# ESP32-S3-UNO_Easyeda_pro.net
KiCad netlist of a schematic drawn in EasyEDA Pro
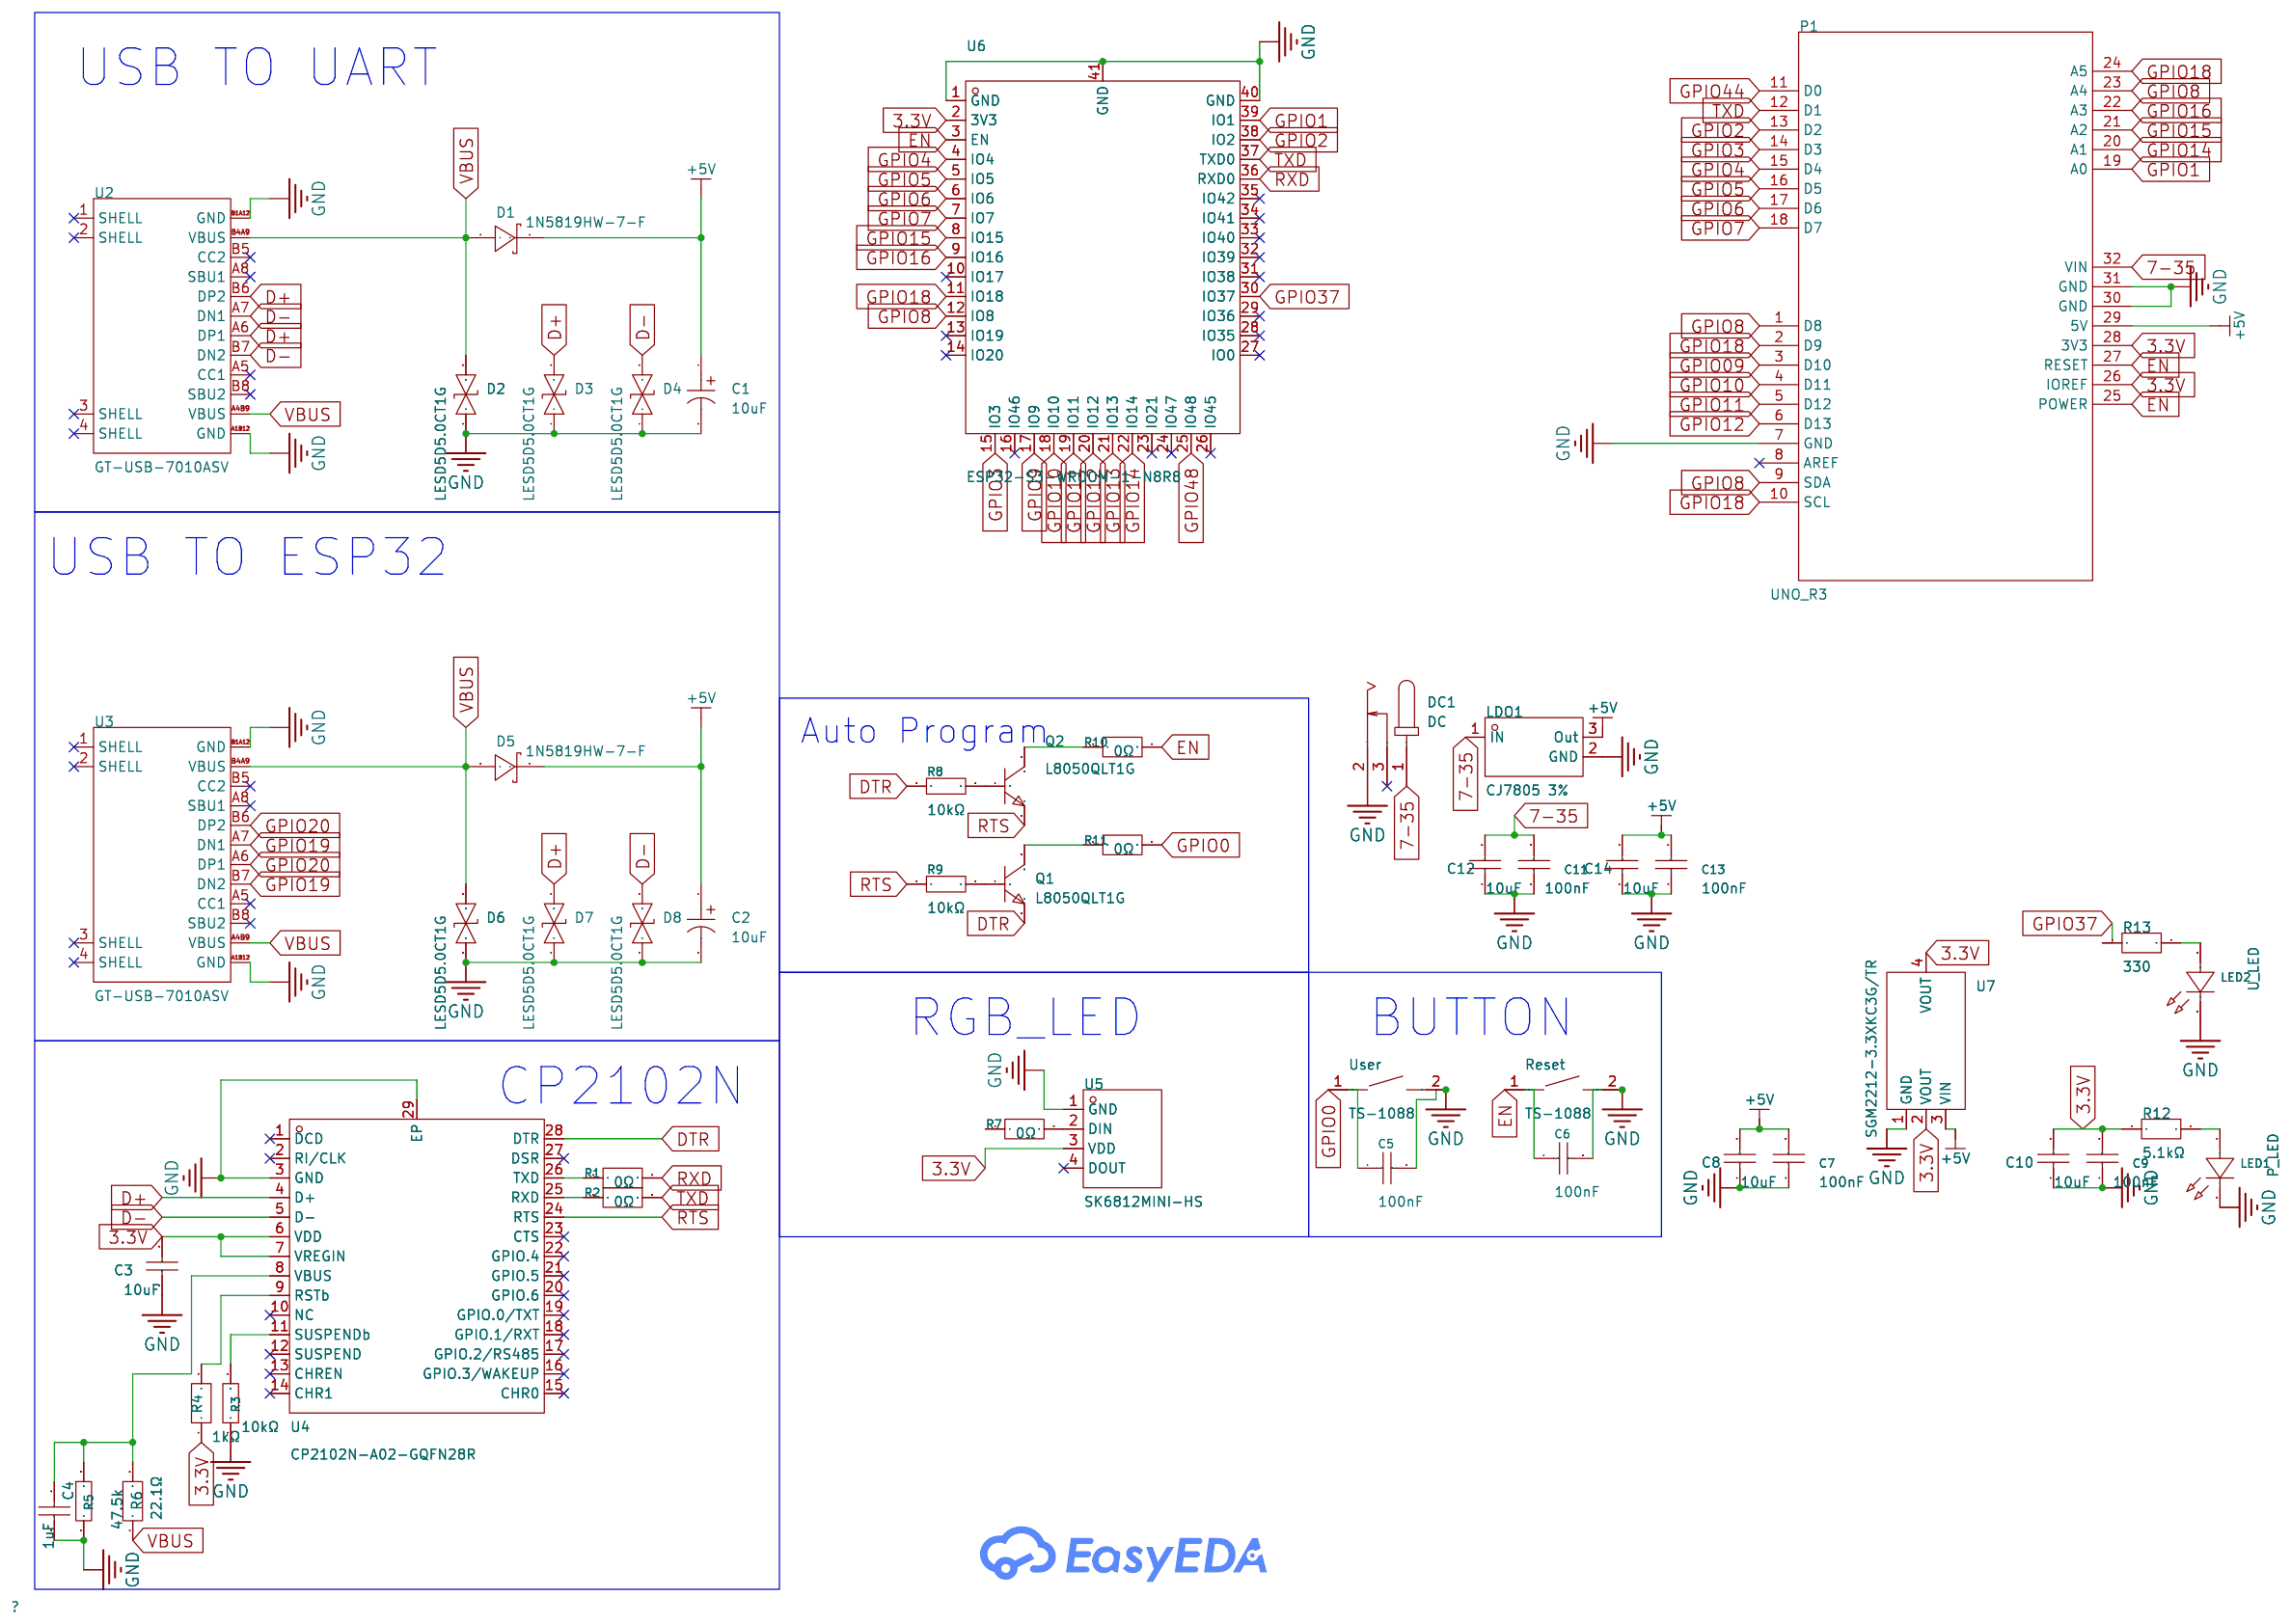
[diagram p0: schematic sheet]

(export (version "E")
  (design (tool "Eeschema 10.0.6"))
  (components
    (comp (ref "C1")
      (value "10uF")
      (footprint "easyedapro:CAP-SMD_BD4.0-L4.3-W4.3-FD-LS5.3")
      (fields
        (field (name "Manufacturer Part") "EFVH025ADA100M0454")
        (field (name "Manufacturer") "FOLLON(富隆电子)")
      )
      (libsource (lib "easyedapro") (part "EFVH025ADA100M0454"))
    )
    (comp (ref "C2")
      (value "10uF")
      (footprint "easyedapro:CAP-SMD_BD4.0-L4.3-W4.3-FD-LS5.3")
      (fields
        (field (name "Manufacturer Part") "EFVH025ADA100M0454")
        (field (name "Manufacturer") "FOLLON(富隆电子)")
      )
      (libsource (lib "easyedapro") (part "EFVH025ADA100M0454"))
    )
    (comp (ref "C3")
      (value "10uF")
      (footprint "easyedapro:C1206")
      (fields
        (field (name "Manufacturer Part") "CL31A106KBHNNNE")
        (field (name "Manufacturer") "SAMSUNG(三星)")
      )
      (libsource (lib "easyedapro") (part "CL31A106KBHNNNE"))
    )
    (comp (ref "C4")
      (value "1uF")
      (footprint "easyedapro:C1206")
      (fields
        (field (name "Manufacturer Part") "CL31B105KAHNNNE")
        (field (name "Manufacturer") "SAMSUNG(三星)")
      )
      (libsource (lib "easyedapro") (part "CL31B105KAHNNNE"))
    )
    (comp (ref "C5")
      (value "100nF")
      (footprint "easyedapro:C1206")
      (fields
        (field (name "Manufacturer Part") "CL31B104KBCNNNC")
        (field (name "Manufacturer") "SAMSUNG(三星)")
      )
      (libsource (lib "easyedapro") (part "CL31B104KBCNNNC"))
    )
    (comp (ref "C6")
      (value "100nF")
      (footprint "easyedapro:C1206")
      (fields
        (field (name "Manufacturer Part") "CL31B104KBCNNNC")
        (field (name "Manufacturer") "SAMSUNG(三星)")
      )
      (libsource (lib "easyedapro") (part "CL31B104KBCNNNC"))
    )
    (comp (ref "C7")
      (value "100nF")
      (footprint "easyedapro:C1206")
      (fields
        (field (name "Manufacturer Part") "CL31B104KBCNNNC")
        (field (name "Manufacturer") "SAMSUNG(三星)")
      )
      (libsource (lib "easyedapro") (part "CL31B104KBCNNNC"))
    )
    (comp (ref "C8")
      (value "10uF")
      (footprint "easyedapro:C1206")
      (fields
        (field (name "Manufacturer Part") "CL31A106KBHNNNE")
        (field (name "Manufacturer") "SAMSUNG(三星)")
      )
      (libsource (lib "easyedapro") (part "CL31A106KBHNNNE"))
    )
    (comp (ref "C9")
      (value "100nF")
      (footprint "easyedapro:C1206")
      (fields
        (field (name "Manufacturer Part") "CL31B104KBCNNNC")
        (field (name "Manufacturer") "SAMSUNG(三星)")
      )
      (libsource (lib "easyedapro") (part "CL31B104KBCNNNC"))
    )
    (comp (ref "C10")
      (value "10uF")
      (footprint "easyedapro:C1206")
      (fields
        (field (name "Manufacturer Part") "CL31A106KBHNNNE")
        (field (name "Manufacturer") "SAMSUNG(三星)")
      )
      (libsource (lib "easyedapro") (part "CL31A106KBHNNNE"))
    )
    (comp (ref "C11")
      (value "100nF")
      (footprint "easyedapro:C1206")
      (fields
        (field (name "Manufacturer Part") "CL31B104KBCNNNC")
        (field (name "Manufacturer") "SAMSUNG(三星)")
      )
      (libsource (lib "easyedapro") (part "CL31B104KBCNNNC"))
    )
    (comp (ref "C12")
      (value "10uF")
      (footprint "easyedapro:C1206")
      (fields
        (field (name "Manufacturer Part") "CL31A106KBHNNNE")
        (field (name "Manufacturer") "SAMSUNG(三星)")
      )
      (libsource (lib "easyedapro") (part "CL31A106KBHNNNE"))
    )
    (comp (ref "C13")
      (value "100nF")
      (footprint "easyedapro:C1206")
      (fields
        (field (name "Manufacturer Part") "CL31B104KBCNNNC")
        (field (name "Manufacturer") "SAMSUNG(三星)")
      )
      (libsource (lib "easyedapro") (part "CL31B104KBCNNNC"))
    )
    (comp (ref "C14")
      (value "10uF")
      (footprint "easyedapro:C1206")
      (fields
        (field (name "Manufacturer Part") "CL31A106KBHNNNE")
        (field (name "Manufacturer") "SAMSUNG(三星)")
      )
      (libsource (lib "easyedapro") (part "CL31A106KBHNNNE"))
    )
    (comp (ref "D1")
      (value "1N5819HW-7-F")
      (footprint "easyedapro:SOD-123_L2.7-W1.6-LS3.7-RD")
      (fields (field (name "Manufacturer") "DIODES(美台)"))
      (libsource (lib "easyedapro") (part "1N5819HW-7-F"))
    )
    (comp (ref "D2")
      (value "LESD5D5.0CT1G")
      (footprint "easyedapro:SOD-523_L1.2-W0.8-LS1.6-BI")
      (fields (field (name "Manufacturer") "LRC(乐山无线电)"))
      (libsource (lib "easyedapro") (part "LESD5D5.0CT1G"))
    )
    (comp (ref "D3")
      (value "LESD5D5.0CT1G")
      (footprint "easyedapro:SOD-523_L1.2-W0.8-LS1.6-BI")
      (fields (field (name "Manufacturer") "LRC(乐山无线电)"))
      (libsource (lib "easyedapro") (part "LESD5D5.0CT1G"))
    )
    (comp (ref "D4")
      (value "LESD5D5.0CT1G")
      (footprint "easyedapro:SOD-523_L1.2-W0.8-LS1.6-BI")
      (fields (field (name "Manufacturer") "LRC(乐山无线电)"))
      (libsource (lib "easyedapro") (part "LESD5D5.0CT1G"))
    )
    (comp (ref "D5")
      (value "1N5819HW-7-F")
      (footprint "easyedapro:SOD-123_L2.7-W1.6-LS3.7-RD")
      (fields (field (name "Manufacturer") "DIODES(美台)"))
      (libsource (lib "easyedapro") (part "1N5819HW-7-F"))
    )
    (comp (ref "D6")
      (value "LESD5D5.0CT1G")
      (footprint "easyedapro:SOD-523_L1.2-W0.8-LS1.6-BI")
      (fields (field (name "Manufacturer") "LRC(乐山无线电)"))
      (libsource (lib "easyedapro") (part "LESD5D5.0CT1G"))
    )
    (comp (ref "D7")
      (value "LESD5D5.0CT1G")
      (footprint "easyedapro:SOD-523_L1.2-W0.8-LS1.6-BI")
      (fields (field (name "Manufacturer") "LRC(乐山无线电)"))
      (libsource (lib "easyedapro") (part "LESD5D5.0CT1G"))
    )
    (comp (ref "D8")
      (value "LESD5D5.0CT1G")
      (footprint "easyedapro:SOD-523_L1.2-W0.8-LS1.6-BI")
      (fields (field (name "Manufacturer") "LRC(乐山无线电)"))
      (libsource (lib "easyedapro") (part "LESD5D5.0CT1G"))
    )
    (comp (ref "DC1")
      (value "DC")
      (footprint "easyedapro:DC-IN-TH_DC005")
      (fields (field (name "Manufacturer") "Ckmtw(灿科盟)"))
      (libsource (lib "easyedapro") (part "dc-005 5.5-2.0"))
    )
    (comp (ref "LDO1")
      (value "CJ7805 3%")
      (footprint "easyedapro:TO-252-2_L6.6-W6.1-P4.58-LS10.1-BR-CW")
      (fields (field (name "Manufacturer") "CJ(江苏长电/长晶)"))
      (libsource (lib "easyedapro") (part "CJ7805 3%"))
    )
    (comp (ref "LED1")
      (value "P_LED")
      (footprint "easyedapro:LED1206-R-RD_RED")
      (fields (field (name "Manufacturer") "XINGLIGHT(成兴光)"))
      (libsource (lib "easyedapro") (part "XL-3216SURC"))
    )
    (comp (ref "LED2")
      (value "U_LED")
      (footprint "easyedapro:LED1206-R-RD_RED")
      (fields (field (name "Manufacturer") "XINGLIGHT(成兴光)"))
      (libsource (lib "easyedapro") (part "XL-3216SURC"))
    )
    (comp (ref "P1")
      (value "UNO_R3")
      (footprint "easyedapro:UNO_R3")
      (libsource (lib "easyedapro") (part "UNO_R3"))
    )
    (comp (ref "Q1")
      (value "L8050QLT1G")
      (footprint "easyedapro:SOT-23-3_L2.9-W1.3-P1.90-LS2.4-BR")
      (fields (field (name "Manufacturer") "LRC(乐山无线电)"))
      (libsource (lib "easyedapro") (part "L8050QLT1G"))
    )
    (comp (ref "Q2")
      (value "L8050QLT1G")
      (footprint "easyedapro:SOT-23-3_L2.9-W1.3-P1.90-LS2.4-BR")
      (fields (field (name "Manufacturer") "LRC(乐山无线电)"))
      (libsource (lib "easyedapro") (part "L8050QLT1G"))
    )
    (comp (ref "R1")
      (value "0Ω")
      (footprint "easyedapro:R1206")
      (fields (field (name "Manufacturer Part") "FRC1206P000 TS") (field (name "Manufacturer") "FOJAN(富捷)"))
      (libsource (lib "easyedapro") (part "FRC1206P000 TS"))
    )
    (comp (ref "R2")
      (value "0Ω")
      (footprint "easyedapro:R1206")
      (fields (field (name "Manufacturer Part") "FRC1206P000 TS") (field (name "Manufacturer") "FOJAN(富捷)"))
      (libsource (lib "easyedapro") (part "FRC1206P000 TS"))
    )
    (comp (ref "R3")
      (value "10kΩ")
      (footprint "easyedapro:R1206")
      (fields
        (field (name "Manufacturer Part") "1206W4F1002T5E")
        (field (name "Manufacturer") "UNI-ROYAL(厚声)")
      )
      (libsource (lib "easyedapro") (part "1206W4F1002T5E"))
    )
    (comp (ref "R4")
      (value "1kΩ")
      (footprint "easyedapro:R1206")
      (fields (field (name "Manufacturer Part") "FRC1206J102 TS") (field (name "Manufacturer") "FOJAN(富捷)"))
      (libsource (lib "easyedapro") (part "FRC1206J102 TS"))
    )
    (comp (ref "R5")
      (value "47.5k")
      (footprint "easyedapro:R1206")
      (fields
        (field (name "Manufacturer Part") "1206W4F1002T5E")
        (field (name "Manufacturer") "UNI-ROYAL(厚声)")
      )
      (libsource (lib "easyedapro") (part "1206W4F1002T5E"))
    )
    (comp (ref "R6")
      (value "22.1Ω")
      (footprint "easyedapro:R1206")
      (fields (field (name "Manufacturer Part") "RC1206FR-0722R1L") (field (name "Manufacturer") "YAGEO(国巨)"))
      (libsource (lib "easyedapro") (part "RC1206FR-0722R1L"))
    )
    (comp (ref "R7")
      (value "0Ω")
      (footprint "easyedapro:R1206")
      (fields (field (name "Manufacturer Part") "FRC1206P000 TS") (field (name "Manufacturer") "FOJAN(富捷)"))
      (libsource (lib "easyedapro") (part "FRC1206P000 TS"))
    )
    (comp (ref "R8")
      (value "10kΩ")
      (footprint "easyedapro:R1206")
      (fields
        (field (name "Manufacturer Part") "1206W4F1002T5E")
        (field (name "Manufacturer") "UNI-ROYAL(厚声)")
      )
      (libsource (lib "easyedapro") (part "1206W4F1002T5E"))
    )
    (comp (ref "R9")
      (value "10kΩ")
      (footprint "easyedapro:R1206")
      (fields
        (field (name "Manufacturer Part") "1206W4F1002T5E")
        (field (name "Manufacturer") "UNI-ROYAL(厚声)")
      )
      (libsource (lib "easyedapro") (part "1206W4F1002T5E"))
    )
    (comp (ref "R10")
      (value "0Ω")
      (footprint "easyedapro:R1206")
      (fields (field (name "Manufacturer Part") "FRC1206P000 TS") (field (name "Manufacturer") "FOJAN(富捷)"))
      (libsource (lib "easyedapro") (part "FRC1206P000 TS"))
    )
    (comp (ref "R11")
      (value "0Ω")
      (footprint "easyedapro:R1206")
      (fields (field (name "Manufacturer Part") "FRC1206P000 TS") (field (name "Manufacturer") "FOJAN(富捷)"))
      (libsource (lib "easyedapro") (part "FRC1206P000 TS"))
    )
    (comp (ref "R12")
      (value "5.1kΩ")
      (footprint "easyedapro:R1206")
      (fields (field (name "Manufacturer Part") "FRC1206J512 TS") (field (name "Manufacturer") "FOJAN(富捷)"))
      (libsource (lib "easyedapro") (part "FRC1206J512 TS"))
    )
    (comp (ref "R13")
      (value "330")
      (footprint "easyedapro:R1206")
      (fields (field (name "Manufacturer Part") "FRC1206J512 TS") (field (name "Manufacturer") "FOJAN(富捷)"))
      (libsource (lib "easyedapro") (part "FRC1206J512 TS"))
    )
    (comp (ref "Reset")
      (value "TS-1088")
      (footprint "easyedapro:SW-SMD_L3.9-W3.0-P4.45")
      (fields (field (name "Manufacturer") "XUNPU(讯普)"))
      (libsource (lib "easyedapro") (part "TS-1088-AR02016"))
    )
    (comp (ref "U2")
      (value "GT-USB-7010ASV")
      (footprint "easyedapro:USB-C-SMD_G-SWITCH_GT-USB-7010ASV")
      (fields (field (name "Manufacturer") "G-Switch(品赞)"))
      (libsource (lib "easyedapro") (part "GT-USB-7010ASV"))
    )
    (comp (ref "U3")
      (value "GT-USB-7010ASV")
      (footprint "easyedapro:USB-C-SMD_G-SWITCH_GT-USB-7010ASV")
      (fields (field (name "Manufacturer") "G-Switch(品赞)"))
      (libsource (lib "easyedapro") (part "GT-USB-7010ASV"))
    )
    (comp (ref "U4")
      (value "CP2102N-A02-GQFN28R")
      (footprint "easyedapro:QFN-28_L5.0-W5.0-P0.50-TL-EP3.3")
      (fields (field (name "Manufacturer") "SKYWORKS/SILICON LABS(芯科)"))
      (libsource (lib "easyedapro") (part "CP2102N-A02-GQFN28R"))
    )
    (comp (ref "U5")
      (value "SK6812MINI-HS")
      (footprint "easyedapro:LED-SMD_4P-L3.5-W3.5-BR_SK6812MINI-HS")
      (fields (field (name "Manufacturer") "欧思科光电"))
      (libsource (lib "easyedapro") (part "SK6812MINI-HS"))
    )
    (comp (ref "U6")
      (value "ESP32-S3-WROOM-1-N8R8")
      (footprint "easyedapro:WIRELM-SMD_ESP32-S3-WROOM-1")
      (fields (field (name "Manufacturer") "ESPRESSIF(乐鑫)"))
      (libsource (lib "easyedapro") (part "ESP32-S3-WROOM-1(N8R8)"))
    )
    (comp (ref "U7")
      (value "SGM2212-3.3XKC3G/TR")
      (footprint "easyedapro:SOT-223-3_L6.5-W3.4-P2.30-LS7.0-BR")
      (fields (field (name "Manufacturer") "SGMICRO(圣邦微)"))
      (libsource (lib "easyedapro") (part "SGM2212-3.3XKC3G/TR_C3294699"))
    )
    (comp (ref "User")
      (value "TS-1088")
      (footprint "easyedapro:SW-SMD_L3.9-W3.0-P4.45")
      (fields (field (name "Manufacturer") "XUNPU(讯普)"))
      (libsource (lib "easyedapro") (part "TS-1088-AR02016"))
    )
  )
  (nets
    (net (code "1") (name "+5V") (class "Default")
      (node (ref "C1") (pin "1") (pinfunction "1_1") (pintype "input"))
      (node (ref "C13") (pin "2") (pinfunction "2_2") (pintype "input"))
      (node (ref "C14") (pin "2") (pinfunction "2_2") (pintype "input"))
      (node (ref "C2") (pin "1") (pinfunction "1_1") (pintype "input"))
      (node (ref "C7") (pin "2") (pinfunction "2_2") (pintype "input"))
      (node (ref "C8") (pin "2") (pinfunction "2_2") (pintype "input"))
      (node (ref "D1") (pin "1") (pinfunction "K_1") (pintype "unspecified"))
      (node (ref "D5") (pin "1") (pinfunction "K_1") (pintype "unspecified"))
      (node (ref "LDO1") (pin "3") (pinfunction "Out_3") (pintype "unspecified"))
      (node (ref "P1") (pin "29") (pinfunction "5V_29") (pintype "unspecified"))
      (node (ref "U7") (pin "3") (pinfunction "VIN_3") (pintype "unspecified"))
    )
    (net (code "2") (name "3.3V") (class "Default")
      (node (ref "C10") (pin "2") (pinfunction "2_2") (pintype "input"))
      (node (ref "C3") (pin "2") (pinfunction "2_2") (pintype "input"))
      (node (ref "C9") (pin "2") (pinfunction "2_2") (pintype "input"))
      (node (ref "P1") (pin "26") (pinfunction "IOREF_26") (pintype "unspecified"))
      (node (ref "P1") (pin "28") (pinfunction "3V3_28") (pintype "unspecified"))
      (node (ref "R12") (pin "1") (pinfunction "1_1") (pintype "unspecified"))
      (node (ref "R4") (pin "1") (pinfunction "1_1") (pintype "unspecified"))
      (node (ref "U4") (pin "6") (pinfunction "VDD_6") (pintype "unspecified"))
      (node (ref "U4") (pin "7") (pinfunction "VREGIN_7") (pintype "unspecified"))
      (node (ref "U5") (pin "3") (pinfunction "VDD_3") (pintype "unspecified"))
      (node (ref "U6") (pin "2") (pinfunction "3V3_2") (pintype "unspecified"))
      (node (ref "U7") (pin "2") (pinfunction "VOUT_2") (pintype "unspecified"))
      (node (ref "U7") (pin "4") (pinfunction "VOUT_4") (pintype "unspecified"))
    )
    (net (code "3") (name "7-35") (class "Default")
      (node (ref "C11") (pin "2") (pinfunction "2_2") (pintype "input"))
      (node (ref "C12") (pin "2") (pinfunction "2_2") (pintype "input"))
      (node (ref "DC1") (pin "1") (pinfunction "1_1") (pintype "unspecified"))
      (node (ref "LDO1") (pin "1") (pinfunction "IN_1") (pintype "unspecified"))
      (node (ref "P1") (pin "32") (pinfunction "VIN_32") (pintype "unspecified"))
    )
    (net (code "4") (name "D+") (class "Default")
      (node (ref "D3") (pin "2") (pinfunction "2_2") (pintype "unspecified"))
      (node (ref "D7") (pin "2") (pinfunction "2_2") (pintype "unspecified"))
      (node (ref "U2") (pin "A6") (pinfunction "DP1_A6") (pintype "unspecified"))
      (node (ref "U2") (pin "B6") (pinfunction "DP2_B6") (pintype "unspecified"))
      (node (ref "U4") (pin "4") (pinfunction "D+_4") (pintype "unspecified"))
    )
    (net (code "5") (name "D-") (class "Default")
      (node (ref "D4") (pin "2") (pinfunction "2_2") (pintype "unspecified"))
      (node (ref "D8") (pin "2") (pinfunction "2_2") (pintype "unspecified"))
      (node (ref "U2") (pin "A7") (pinfunction "DN1_A7") (pintype "unspecified"))
      (node (ref "U2") (pin "B7") (pinfunction "DN2_B7") (pintype "unspecified"))
      (node (ref "U4") (pin "5") (pinfunction "D-_5") (pintype "unspecified"))
    )
    (net (code "6") (name "DTR") (class "Default")
      (node (ref "Q1") (pin "2") (pinfunction "E_2") (pintype "unspecified"))
      (node (ref "R8") (pin "2") (pinfunction "2_2") (pintype "input"))
      (node (ref "U4") (pin "28") (pinfunction "DTR_28") (pintype "unspecified"))
    )
    (net (code "7") (name "EN") (class "Default")
      (node (ref "C6") (pin "1") (pinfunction "1_1") (pintype "input"))
      (node (ref "P1") (pin "25") (pinfunction "POWER_25") (pintype "unspecified"))
      (node (ref "P1") (pin "27") (pinfunction "RESET_27") (pintype "unspecified"))
      (node (ref "R10") (pin "2") (pinfunction "2_2") (pintype "input"))
      (node (ref "Reset") (pin "1") (pinfunction "1_1") (pintype "unspecified"))
      (node (ref "U6") (pin "3") (pinfunction "EN_3") (pintype "unspecified"))
    )
    (net (code "8") (name "GND") (class "Default")
      (node (ref "C1") (pin "2") (pinfunction "2_2") (pintype "input"))
      (node (ref "C10") (pin "1") (pinfunction "1_1") (pintype "input"))
      (node (ref "C11") (pin "1") (pinfunction "1_1") (pintype "input"))
      (node (ref "C12") (pin "1") (pinfunction "1_1") (pintype "input"))
      (node (ref "C13") (pin "1") (pinfunction "1_1") (pintype "input"))
      (node (ref "C14") (pin "1") (pinfunction "1_1") (pintype "input"))
      (node (ref "C2") (pin "2") (pinfunction "2_2") (pintype "input"))
      (node (ref "C3") (pin "1") (pinfunction "1_1") (pintype "input"))
      (node (ref "C4") (pin "1") (pinfunction "1_1") (pintype "input"))
      (node (ref "C5") (pin "2") (pinfunction "2_2") (pintype "input"))
      (node (ref "C6") (pin "2") (pinfunction "2_2") (pintype "input"))
      (node (ref "C7") (pin "1") (pinfunction "1_1") (pintype "input"))
      (node (ref "C8") (pin "1") (pinfunction "1_1") (pintype "input"))
      (node (ref "C9") (pin "1") (pinfunction "1_1") (pintype "input"))
      (node (ref "D2") (pin "1") (pinfunction "1_1") (pintype "unspecified"))
      (node (ref "D3") (pin "1") (pinfunction "1_1") (pintype "unspecified"))
      (node (ref "D4") (pin "1") (pinfunction "1_1") (pintype "unspecified"))
      (node (ref "D6") (pin "1") (pinfunction "1_1") (pintype "unspecified"))
      (node (ref "D7") (pin "1") (pinfunction "1_1") (pintype "unspecified"))
      (node (ref "D8") (pin "1") (pinfunction "1_1") (pintype "unspecified"))
      (node (ref "DC1") (pin "2") (pinfunction "2_2") (pintype "unspecified"))
      (node (ref "LDO1") (pin "2") (pinfunction "GND_2") (pintype "unspecified"))
      (node (ref "LED1") (pin "2") (pinfunction "A_2") (pintype "input"))
      (node (ref "LED2") (pin "2") (pinfunction "A_2") (pintype "input"))
      (node (ref "P1") (pin "30") (pinfunction "GND_30") (pintype "unspecified"))
      (node (ref "P1") (pin "31") (pinfunction "GND_31") (pintype "unspecified"))
      (node (ref "P1") (pin "7") (pinfunction "GND_7") (pintype "unspecified"))
      (node (ref "R3") (pin "1") (pinfunction "1_1") (pintype "input"))
      (node (ref "R5") (pin "1") (pinfunction "1_1") (pintype "input"))
      (node (ref "Reset") (pin "2") (pinfunction "2_2") (pintype "unspecified"))
      (node (ref "U2") (pin "A1B12") (pinfunction "GND_A1B12") (pintype "unspecified"))
      (node (ref "U2") (pin "B1A12") (pinfunction "GND_B1A12") (pintype "unspecified"))
      (node (ref "U3") (pin "A1B12") (pinfunction "GND_A1B12") (pintype "unspecified"))
      (node (ref "U3") (pin "B1A12") (pinfunction "GND_B1A12") (pintype "unspecified"))
      (node (ref "U4") (pin "29") (pinfunction "EP_29") (pintype "unspecified"))
      (node (ref "U4") (pin "3") (pinfunction "GND_3") (pintype "unspecified"))
      (node (ref "U5") (pin "1") (pinfunction "GND_1") (pintype "unspecified"))
      (node (ref "U6") (pin "1") (pinfunction "GND_1") (pintype "unspecified"))
      (node (ref "U6") (pin "40") (pinfunction "GND_40") (pintype "unspecified"))
      (node (ref "U6") (pin "41") (pinfunction "GND_41") (pintype "unspecified"))
      (node (ref "U7") (pin "1") (pinfunction "GND_1") (pintype "unspecified"))
      (node (ref "User") (pin "2") (pinfunction "2_2") (pintype "unspecified"))
    )
    (net (code "9") (name "GPIO0") (class "Default")
      (node (ref "C5") (pin "1") (pinfunction "1_1") (pintype "input"))
      (node (ref "R11") (pin "2") (pinfunction "2_2") (pintype "input"))
      (node (ref "User") (pin "1") (pinfunction "1_1") (pintype "unspecified"))
    )
    (net (code "10") (name "GPIO1") (class "Default")
      (node (ref "P1") (pin "19") (pinfunction "A0_19") (pintype "unspecified"))
      (node (ref "U6") (pin "39") (pinfunction "IO1_39") (pintype "unspecified"))
    )
    (net (code "11") (name "GPIO2") (class "Default")
      (node (ref "P1") (pin "13") (pinfunction "D2_13") (pintype "unspecified"))
      (node (ref "U6") (pin "38") (pinfunction "IO2_38") (pintype "unspecified"))
    )
    (net (code "12") (name "GPIO3") (class "Default")
      (node (ref "P1") (pin "14") (pinfunction "D3_14") (pintype "unspecified"))
      (node (ref "U6") (pin "15") (pinfunction "IO3_15") (pintype "unspecified"))
    )
    (net (code "13") (name "GPIO4") (class "Default")
      (node (ref "P1") (pin "15") (pinfunction "D4_15") (pintype "unspecified"))
      (node (ref "U6") (pin "4") (pinfunction "IO4_4") (pintype "unspecified"))
    )
    (net (code "14") (name "GPIO5") (class "Default")
      (node (ref "P1") (pin "16") (pinfunction "D5_16") (pintype "unspecified"))
      (node (ref "U6") (pin "5") (pinfunction "IO5_5") (pintype "unspecified"))
    )
    (net (code "15") (name "GPIO6") (class "Default")
      (node (ref "P1") (pin "17") (pinfunction "D6_17") (pintype "unspecified"))
      (node (ref "U6") (pin "6") (pinfunction "IO6_6") (pintype "unspecified"))
    )
    (net (code "16") (name "GPIO7") (class "Default")
      (node (ref "P1") (pin "18") (pinfunction "D7_18") (pintype "unspecified"))
      (node (ref "U6") (pin "7") (pinfunction "IO7_7") (pintype "unspecified"))
    )
    (net (code "17") (name "GPIO8") (class "Default")
      (node (ref "P1") (pin "1") (pinfunction "D8_1") (pintype "unspecified"))
      (node (ref "P1") (pin "23") (pinfunction "A4_23") (pintype "unspecified"))
      (node (ref "P1") (pin "9") (pinfunction "SDA_9") (pintype "unspecified"))
      (node (ref "U6") (pin "12") (pinfunction "IO8_12") (pintype "unspecified"))
    )
    (net (code "18") (name "GPIO9") (class "Default")
      (node (ref "U6") (pin "17") (pinfunction "IO9_17") (pintype "unspecified"))
    )
    (net (code "19") (name "GPIO09") (class "Default")
      (node (ref "P1") (pin "3") (pinfunction "D10_3") (pintype "unspecified"))
    )
    (net (code "20") (name "GPIO10") (class "Default")
      (node (ref "P1") (pin "4") (pinfunction "D11_4") (pintype "unspecified"))
      (node (ref "U6") (pin "18") (pinfunction "IO10_18") (pintype "unspecified"))
    )
    (net (code "21") (name "GPIO11") (class "Default")
      (node (ref "P1") (pin "5") (pinfunction "D12_5") (pintype "unspecified"))
      (node (ref "U6") (pin "19") (pinfunction "IO11_19") (pintype "unspecified"))
    )
    (net (code "22") (name "GPIO12") (class "Default")
      (node (ref "P1") (pin "6") (pinfunction "D13_6") (pintype "unspecified"))
      (node (ref "U6") (pin "20") (pinfunction "IO12_20") (pintype "unspecified"))
    )
    (net (code "23") (name "GPIO13") (class "Default")
      (node (ref "U6") (pin "21") (pinfunction "IO13_21") (pintype "unspecified"))
    )
    (net (code "24") (name "GPIO14") (class "Default")
      (node (ref "P1") (pin "20") (pinfunction "A1_20") (pintype "unspecified"))
      (node (ref "U6") (pin "22") (pinfunction "IO14_22") (pintype "unspecified"))
    )
    (net (code "25") (name "GPIO15") (class "Default")
      (node (ref "P1") (pin "21") (pinfunction "A2_21") (pintype "unspecified"))
      (node (ref "U6") (pin "8") (pinfunction "IO15_8") (pintype "unspecified"))
    )
    (net (code "26") (name "GPIO16") (class "Default")
      (node (ref "P1") (pin "22") (pinfunction "A3_22") (pintype "unspecified"))
      (node (ref "U6") (pin "9") (pinfunction "IO16_9") (pintype "unspecified"))
    )
    (net (code "27") (name "GPIO18") (class "Default")
      (node (ref "P1") (pin "10") (pinfunction "SCL_10") (pintype "unspecified"))
      (node (ref "P1") (pin "2") (pinfunction "D9_2") (pintype "unspecified"))
      (node (ref "P1") (pin "24") (pinfunction "A5_24") (pintype "unspecified"))
      (node (ref "U6") (pin "11") (pinfunction "IO18_11") (pintype "unspecified"))
    )
    (net (code "28") (name "GPIO19") (class "Default")
      (node (ref "U3") (pin "A7") (pinfunction "DN1_A7") (pintype "unspecified"))
      (node (ref "U3") (pin "B7") (pinfunction "DN2_B7") (pintype "unspecified"))
    )
    (net (code "29") (name "GPIO20") (class "Default")
      (node (ref "U3") (pin "A6") (pinfunction "DP1_A6") (pintype "unspecified"))
      (node (ref "U3") (pin "B6") (pinfunction "DP2_B6") (pintype "unspecified"))
    )
    (net (code "30") (name "GPIO37") (class "Default")
      (node (ref "R13") (pin "1") (pinfunction "1_1") (pintype "unspecified"))
      (node (ref "U6") (pin "30") (pinfunction "IO37_30") (pintype "unspecified"))
    )
    (net (code "31") (name "GPIO44") (class "Default")
      (node (ref "P1") (pin "11") (pinfunction "D0_11") (pintype "unspecified"))
    )
    (net (code "32") (name "GPIO48") (class "Default")
      (node (ref "U6") (pin "25") (pinfunction "IO48_25") (pintype "unspecified"))
    )
    (net (code "33") (name "Net-(LED1-K)") (class "Default")
      (node (ref "LED1") (pin "1") (pinfunction "K_1") (pintype "input"))
      (node (ref "R12") (pin "2") (pinfunction "2_2") (pintype "unspecified"))
    )
    (net (code "34") (name "Net-(LED2-K)") (class "Default")
      (node (ref "LED2") (pin "1") (pinfunction "K_1") (pintype "input"))
      (node (ref "R13") (pin "2") (pinfunction "2_2") (pintype "unspecified"))
    )
    (net (code "35") (name "Net-(Q1-B)") (class "Default")
      (node (ref "Q1") (pin "1") (pinfunction "B_1") (pintype "unspecified"))
      (node (ref "R9") (pin "1") (pinfunction "1_1") (pintype "input"))
    )
    (net (code "36") (name "Net-(Q1-C)") (class "Default")
      (node (ref "Q1") (pin "3") (pinfunction "C_3") (pintype "unspecified"))
      (node (ref "R11") (pin "1") (pinfunction "1_1") (pintype "input"))
    )
    (net (code "37") (name "Net-(Q2-B)") (class "Default")
      (node (ref "Q2") (pin "1") (pinfunction "B_1") (pintype "unspecified"))
      (node (ref "R8") (pin "1") (pinfunction "1_1") (pintype "input"))
    )
    (net (code "38") (name "Net-(Q2-C)") (class "Default")
      (node (ref "Q2") (pin "3") (pinfunction "C_3") (pintype "unspecified"))
      (node (ref "R10") (pin "1") (pinfunction "1_1") (pintype "input"))
    )
    (net (code "39") (name "Net-(U4-RSTb)") (class "Default")
      (node (ref "R4") (pin "2") (pinfunction "2_2") (pintype "unspecified"))
      (node (ref "U4") (pin "9") (pinfunction "RSTb_9") (pintype "unspecified"))
    )
    (net (code "40") (name "Net-(U4-RXD)") (class "Default")
      (node (ref "R2") (pin "1") (pinfunction "1_1") (pintype "input"))
      (node (ref "U4") (pin "25") (pinfunction "RXD_25") (pintype "unspecified"))
    )
    (net (code "41") (name "Net-(U4-SUSPENDb)") (class "Default")
      (node (ref "R3") (pin "2") (pinfunction "2_2") (pintype "input"))
      (node (ref "U4") (pin "11") (pinfunction "SUSPENDb_11") (pintype "unspecified"))
    )
    (net (code "42") (name "Net-(U4-TXD)") (class "Default")
      (node (ref "R1") (pin "1") (pinfunction "1_1") (pintype "input"))
      (node (ref "U4") (pin "26") (pinfunction "TXD_26") (pintype "unspecified"))
    )
    (net (code "43") (name "Net-(U4-VBUS)") (class "Default")
      (node (ref "C4") (pin "2") (pinfunction "2_2") (pintype "input"))
      (node (ref "R5") (pin "2") (pinfunction "2_2") (pintype "input"))
      (node (ref "R6") (pin "2") (pinfunction "2_2") (pintype "unspecified"))
      (node (ref "U4") (pin "8") (pinfunction "VBUS_8") (pintype "unspecified"))
    )
    (net (code "44") (name "Net-(U5-DIN)") (class "Default")
      (node (ref "R7") (pin "2") (pinfunction "2_2") (pintype "input"))
      (node (ref "U5") (pin "2") (pinfunction "DIN_2") (pintype "unspecified"))
    )
    (net (code "45") (name "RTS") (class "Default")
      (node (ref "Q2") (pin "2") (pinfunction "E_2") (pintype "unspecified"))
      (node (ref "R9") (pin "2") (pinfunction "2_2") (pintype "input"))
      (node (ref "U4") (pin "24") (pinfunction "RTS_24") (pintype "unspecified"))
    )
    (net (code "46") (name "RXD") (class "Default")
      (node (ref "R1") (pin "2") (pinfunction "2_2") (pintype "input"))
      (node (ref "U6") (pin "36") (pinfunction "RXD0_36") (pintype "unspecified"))
    )
    (net (code "47") (name "TXD") (class "Default")
      (node (ref "P1") (pin "12") (pinfunction "D1_12") (pintype "unspecified"))
      (node (ref "R2") (pin "2") (pinfunction "2_2") (pintype "input"))
      (node (ref "U6") (pin "37") (pinfunction "TXD0_37") (pintype "unspecified"))
    )
    (net (code "48") (name "VBUS") (class "Default")
      (node (ref "D1") (pin "2") (pinfunction "A_2") (pintype "unspecified"))
      (node (ref "D2") (pin "2") (pinfunction "2_2") (pintype "unspecified"))
      (node (ref "D5") (pin "2") (pinfunction "A_2") (pintype "unspecified"))
      (node (ref "D6") (pin "2") (pinfunction "2_2") (pintype "unspecified"))
      (node (ref "R6") (pin "1") (pinfunction "1_1") (pintype "unspecified"))
      (node (ref "U2") (pin "A4B9") (pinfunction "VBUS_A4B9") (pintype "unspecified"))
      (node (ref "U2") (pin "B4A9") (pinfunction "VBUS_B4A9") (pintype "unspecified"))
      (node (ref "U3") (pin "A4B9") (pinfunction "VBUS_A4B9") (pintype "unspecified"))
      (node (ref "U3") (pin "B4A9") (pinfunction "VBUS_B4A9") (pintype "unspecified"))
    )
    (net (code "49") (name "unconnected-(DC1-Pad3)") (class "Default")
      (node (ref "DC1") (pin "3") (pinfunction "3_3") (pintype "unspecified+no_connect"))
    )
    (net (code "50") (name "unconnected-(P1-AREF-Pad8)") (class "Default")
      (node (ref "P1") (pin "8") (pinfunction "AREF_8") (pintype "unspecified+no_connect"))
    )
    (net (code "51") (name "unconnected-(R7-Pad1)") (class "Default")
      (node (ref "R7") (pin "1") (pinfunction "1_1") (pintype "input"))
    )
    (net (code "52") (name "unconnected-(U2-CC1-PadA5)") (class "Default")
      (node (ref "U2") (pin "A5") (pinfunction "CC1_A5") (pintype "unspecified+no_connect"))
    )
    (net (code "53") (name "unconnected-(U2-CC2-PadB5)") (class "Default")
      (node (ref "U2") (pin "B5") (pinfunction "CC2_B5") (pintype "unspecified+no_connect"))
    )
    (net (code "54") (name "unconnected-(U2-SBU1-PadA8)") (class "Default")
      (node (ref "U2") (pin "A8") (pinfunction "SBU1_A8") (pintype "unspecified+no_connect"))
    )
    (net (code "55") (name "unconnected-(U2-SBU2-PadB8)") (class "Default")
      (node (ref "U2") (pin "B8") (pinfunction "SBU2_B8") (pintype "unspecified+no_connect"))
    )
    (net (code "56") (name "unconnected-(U2-SHELL-Pad1)") (class "Default")
      (node (ref "U2") (pin "1") (pinfunction "SHELL_1") (pintype "unspecified+no_connect"))
    )
    (net (code "57") (name "unconnected-(U2-SHELL-Pad2)") (class "Default")
      (node (ref "U2") (pin "2") (pinfunction "SHELL_2") (pintype "unspecified+no_connect"))
    )
    (net (code "58") (name "unconnected-(U2-SHELL-Pad3)") (class "Default")
      (node (ref "U2") (pin "3") (pinfunction "SHELL_3") (pintype "unspecified+no_connect"))
    )
    (net (code "59") (name "unconnected-(U2-SHELL-Pad4)") (class "Default")
      (node (ref "U2") (pin "4") (pinfunction "SHELL_4") (pintype "unspecified+no_connect"))
    )
    (net (code "60") (name "unconnected-(U3-CC1-PadA5)") (class "Default")
      (node (ref "U3") (pin "A5") (pinfunction "CC1_A5") (pintype "unspecified+no_connect"))
    )
    (net (code "61") (name "unconnected-(U3-CC2-PadB5)") (class "Default")
      (node (ref "U3") (pin "B5") (pinfunction "CC2_B5") (pintype "unspecified+no_connect"))
    )
    (net (code "62") (name "unconnected-(U3-SBU1-PadA8)") (class "Default")
      (node (ref "U3") (pin "A8") (pinfunction "SBU1_A8") (pintype "unspecified+no_connect"))
    )
    (net (code "63") (name "unconnected-(U3-SBU2-PadB8)") (class "Default")
      (node (ref "U3") (pin "B8") (pinfunction "SBU2_B8") (pintype "unspecified+no_connect"))
    )
    (net (code "64") (name "unconnected-(U3-SHELL-Pad1)") (class "Default")
      (node (ref "U3") (pin "1") (pinfunction "SHELL_1") (pintype "unspecified+no_connect"))
    )
    (net (code "65") (name "unconnected-(U3-SHELL-Pad2)") (class "Default")
      (node (ref "U3") (pin "2") (pinfunction "SHELL_2") (pintype "unspecified+no_connect"))
    )
    (net (code "66") (name "unconnected-(U3-SHELL-Pad3)") (class "Default")
      (node (ref "U3") (pin "3") (pinfunction "SHELL_3") (pintype "unspecified+no_connect"))
    )
    (net (code "67") (name "unconnected-(U3-SHELL-Pad4)") (class "Default")
      (node (ref "U3") (pin "4") (pinfunction "SHELL_4") (pintype "unspecified+no_connect"))
    )
    (net (code "68") (name "unconnected-(U4-CHR0-Pad15)") (class "Default")
      (node (ref "U4") (pin "15") (pinfunction "CHR0_15") (pintype "unspecified+no_connect"))
    )
    (net (code "69") (name "unconnected-(U4-CHR1-Pad14)") (class "Default")
      (node (ref "U4") (pin "14") (pinfunction "CHR1_14") (pintype "unspecified+no_connect"))
    )
    (net (code "70") (name "unconnected-(U4-CHREN-Pad13)") (class "Default")
      (node (ref "U4") (pin "13") (pinfunction "CHREN_13") (pintype "unspecified+no_connect"))
    )
    (net (code "71") (name "unconnected-(U4-CTS-Pad23)") (class "Default")
      (node (ref "U4") (pin "23") (pinfunction "CTS_23") (pintype "unspecified+no_connect"))
    )
    (net (code "72") (name "unconnected-(U4-DCD-Pad1)") (class "Default")
      (node (ref "U4") (pin "1") (pinfunction "DCD_1") (pintype "unspecified+no_connect"))
    )
    (net (code "73") (name "unconnected-(U4-DSR-Pad27)") (class "Default")
      (node (ref "U4") (pin "27") (pinfunction "DSR_27") (pintype "unspecified+no_connect"))
    )
    (net (code "74") (name "unconnected-(U4-GPIO.0{slash}TXT-Pad19)") (class "Default")
      (node (ref "U4") (pin "19") (pinfunction "GPIO.0/TXT_19") (pintype "unspecified+no_connect"))
    )
    (net (code "75") (name "unconnected-(U4-GPIO.1{slash}RXT-Pad18)") (class "Default")
      (node (ref "U4") (pin "18") (pinfunction "GPIO.1/RXT_18") (pintype "unspecified+no_connect"))
    )
    (net (code "76") (name "unconnected-(U4-GPIO.2{slash}RS485-Pad17)") (class "Default")
      (node (ref "U4") (pin "17") (pinfunction "GPIO.2/RS485_17") (pintype "unspecified+no_connect"))
    )
    (net (code "77") (name "unconnected-(U4-GPIO.3{slash}WAKEUP-Pad16)") (class "Default")
      (node (ref "U4") (pin "16") (pinfunction "GPIO.3/WAKEUP_16") (pintype "unspecified+no_connect"))
    )
    (net (code "78") (name "unconnected-(U4-GPIO.4-Pad22)") (class "Default")
      (node (ref "U4") (pin "22") (pinfunction "GPIO.4_22") (pintype "unspecified+no_connect"))
    )
    (net (code "79") (name "unconnected-(U4-GPIO.5-Pad21)") (class "Default")
      (node (ref "U4") (pin "21") (pinfunction "GPIO.5_21") (pintype "unspecified+no_connect"))
    )
    (net (code "80") (name "unconnected-(U4-GPIO.6-Pad20)") (class "Default")
      (node (ref "U4") (pin "20") (pinfunction "GPIO.6_20") (pintype "unspecified+no_connect"))
    )
    (net (code "81") (name "unconnected-(U4-NC-Pad10)") (class "Default")
      (node (ref "U4") (pin "10") (pinfunction "NC_10") (pintype "unspecified+no_connect"))
    )
    (net (code "82") (name "unconnected-(U4-RI{slash}CLK-Pad2)") (class "Default")
      (node (ref "U4") (pin "2") (pinfunction "RI/CLK_2") (pintype "unspecified+no_connect"))
    )
    (net (code "83") (name "unconnected-(U4-SUSPEND-Pad12)") (class "Default")
      (node (ref "U4") (pin "12") (pinfunction "SUSPEND_12") (pintype "unspecified+no_connect"))
    )
    (net (code "84") (name "unconnected-(U5-DOUT-Pad4)") (class "Default")
      (node (ref "U5") (pin "4") (pinfunction "DOUT_4") (pintype "unspecified+no_connect"))
    )
    (net (code "85") (name "unconnected-(U6-IO0-Pad27)") (class "Default")
      (node (ref "U6") (pin "27") (pinfunction "IO0_27") (pintype "unspecified+no_connect"))
    )
    (net (code "86") (name "unconnected-(U6-IO17-Pad10)") (class "Default")
      (node (ref "U6") (pin "10") (pinfunction "IO17_10") (pintype "unspecified+no_connect"))
    )
    (net (code "87") (name "unconnected-(U6-IO19-Pad13)") (class "Default")
      (node (ref "U6") (pin "13") (pinfunction "IO19_13") (pintype "unspecified+no_connect"))
    )
    (net (code "88") (name "unconnected-(U6-IO20-Pad14)") (class "Default")
      (node (ref "U6") (pin "14") (pinfunction "IO20_14") (pintype "unspecified+no_connect"))
    )
    (net (code "89") (name "unconnected-(U6-IO21-Pad23)") (class "Default")
      (node (ref "U6") (pin "23") (pinfunction "IO21_23") (pintype "unspecified+no_connect"))
    )
    (net (code "90") (name "unconnected-(U6-IO35-Pad28)") (class "Default")
      (node (ref "U6") (pin "28") (pinfunction "IO35_28") (pintype "unspecified+no_connect"))
    )
    (net (code "91") (name "unconnected-(U6-IO36-Pad29)") (class "Default")
      (node (ref "U6") (pin "29") (pinfunction "IO36_29") (pintype "unspecified+no_connect"))
    )
    (net (code "92") (name "unconnected-(U6-IO38-Pad31)") (class "Default")
      (node (ref "U6") (pin "31") (pinfunction "IO38_31") (pintype "unspecified+no_connect"))
    )
    (net (code "93") (name "unconnected-(U6-IO39-Pad32)") (class "Default")
      (node (ref "U6") (pin "32") (pinfunction "IO39_32") (pintype "unspecified+no_connect"))
    )
    (net (code "94") (name "unconnected-(U6-IO40-Pad33)") (class "Default")
      (node (ref "U6") (pin "33") (pinfunction "IO40_33") (pintype "unspecified+no_connect"))
    )
    (net (code "95") (name "unconnected-(U6-IO41-Pad34)") (class "Default")
      (node (ref "U6") (pin "34") (pinfunction "IO41_34") (pintype "unspecified+no_connect"))
    )
    (net (code "96") (name "unconnected-(U6-IO42-Pad35)") (class "Default")
      (node (ref "U6") (pin "35") (pinfunction "IO42_35") (pintype "unspecified+no_connect"))
    )
    (net (code "97") (name "unconnected-(U6-IO45-Pad26)") (class "Default")
      (node (ref "U6") (pin "26") (pinfunction "IO45_26") (pintype "unspecified+no_connect"))
    )
    (net (code "98") (name "unconnected-(U6-IO46-Pad16)") (class "Default")
      (node (ref "U6") (pin "16") (pinfunction "IO46_16") (pintype "unspecified+no_connect"))
    )
    (net (code "99") (name "unconnected-(U6-IO47-Pad24)") (class "Default")
      (node (ref "U6") (pin "24") (pinfunction "IO47_24") (pintype "unspecified+no_connect"))
    )
  )
)
